# PJ19.net
KiCad netlist of a schematic drawn in EAGLE
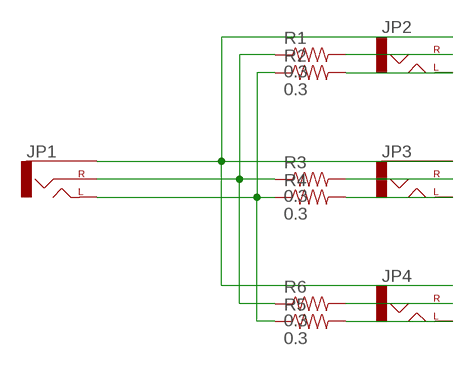
[diagram p0: schematic, sheet 1]

(export (version "E")
  (design (tool "Eeschema 10.0.6"))
  (components
    (comp (ref "JP1")
      (value "AUDIO-JACKPTH")
      (footprint "eagle-import:AUDIO-JACK")
      (libsource (lib "eagle-import") (part "AUDIO-JACKPTH"))
    )
    (comp (ref "JP2")
      (value "AUDIO-JACKPTH")
      (footprint "eagle-import:AUDIO-JACK")
      (libsource (lib "eagle-import") (part "AUDIO-JACKPTH"))
    )
    (comp (ref "JP3")
      (value "AUDIO-JACKPTH")
      (footprint "eagle-import:AUDIO-JACK")
      (libsource (lib "eagle-import") (part "AUDIO-JACKPTH"))
    )
    (comp (ref "JP4")
      (value "AUDIO-JACKPTH")
      (footprint "eagle-import:AUDIO-JACK")
      (libsource (lib "eagle-import") (part "AUDIO-JACKPTH"))
    )
    (comp (ref "R1")
      (value "0.3")
      (footprint "eagle-import:0805")
      (libsource (lib "eagle-import") (part "0.3OHM-1/8W-1%(0805)"))
    )
    (comp (ref "R2")
      (value "0.3")
      (footprint "eagle-import:0805")
      (libsource (lib "eagle-import") (part "0.3OHM-1/8W-1%(0805)"))
    )
    (comp (ref "R3")
      (value "0.3")
      (footprint "eagle-import:0805")
      (libsource (lib "eagle-import") (part "0.3OHM-1/8W-1%(0805)"))
    )
    (comp (ref "R4")
      (value "0.3")
      (footprint "eagle-import:0805")
      (libsource (lib "eagle-import") (part "0.3OHM-1/8W-1%(0805)"))
    )
    (comp (ref "R5")
      (value "0.3")
      (footprint "eagle-import:0805")
      (libsource (lib "eagle-import") (part "0.3OHM-1/8W-1%(0805)"))
    )
    (comp (ref "R6")
      (value "0.3")
      (footprint "eagle-import:0805")
      (libsource (lib "eagle-import") (part "0.3OHM-1/8W-1%(0805)"))
    )
  )
  (nets
    (net (code "1") (name "Net-(JP1-LEFT)") (class "Default")
      (node (ref "JP1") (pin "TIP") (pinfunction "LEFT_TIP") (pintype "bidirectional"))
      (node (ref "R2") (pin "1") (pinfunction "1_1") (pintype "passive"))
      (node (ref "R4") (pin "1") (pinfunction "1_1") (pintype "passive"))
      (node (ref "R5") (pin "1") (pinfunction "1_1") (pintype "passive"))
    )
    (net (code "2") (name "Net-(JP1-PadSLEEVE)") (class "Default")
      (node (ref "JP1") (pin "SLEEVE") (pinfunction "SLEEVE_SLEEVE") (pintype "bidirectional"))
      (node (ref "JP2") (pin "SLEEVE") (pinfunction "SLEEVE_SLEEVE") (pintype "bidirectional"))
      (node (ref "JP3") (pin "SLEEVE") (pinfunction "SLEEVE_SLEEVE") (pintype "bidirectional"))
      (node (ref "JP4") (pin "SLEEVE") (pinfunction "SLEEVE_SLEEVE") (pintype "bidirectional"))
    )
    (net (code "3") (name "Net-(JP1-RIGHT)") (class "Default")
      (node (ref "JP1") (pin "RING") (pinfunction "RIGHT_RING") (pintype "bidirectional"))
      (node (ref "R1") (pin "1") (pinfunction "1_1") (pintype "passive"))
      (node (ref "R3") (pin "1") (pinfunction "1_1") (pintype "passive"))
      (node (ref "R6") (pin "1") (pinfunction "1_1") (pintype "passive"))
    )
    (net (code "4") (name "Net-(JP2-LEFT)") (class "Default")
      (node (ref "JP2") (pin "TIP") (pinfunction "LEFT_TIP") (pintype "bidirectional"))
      (node (ref "R2") (pin "2") (pinfunction "2_2") (pintype "passive"))
    )
    (net (code "5") (name "Net-(JP2-RIGHT)") (class "Default")
      (node (ref "JP2") (pin "RING") (pinfunction "RIGHT_RING") (pintype "bidirectional"))
      (node (ref "R1") (pin "2") (pinfunction "2_2") (pintype "passive"))
    )
    (net (code "6") (name "Net-(JP3-LEFT)") (class "Default")
      (node (ref "JP3") (pin "TIP") (pinfunction "LEFT_TIP") (pintype "bidirectional"))
      (node (ref "R4") (pin "2") (pinfunction "2_2") (pintype "passive"))
    )
    (net (code "7") (name "Net-(JP3-RIGHT)") (class "Default")
      (node (ref "JP3") (pin "RING") (pinfunction "RIGHT_RING") (pintype "bidirectional"))
      (node (ref "R3") (pin "2") (pinfunction "2_2") (pintype "passive"))
    )
    (net (code "8") (name "Net-(JP4-LEFT)") (class "Default")
      (node (ref "JP4") (pin "TIP") (pinfunction "LEFT_TIP") (pintype "bidirectional"))
      (node (ref "R5") (pin "2") (pinfunction "2_2") (pintype "passive"))
    )
    (net (code "9") (name "Net-(JP4-RIGHT)") (class "Default")
      (node (ref "JP4") (pin "RING") (pinfunction "RIGHT_RING") (pintype "bidirectional"))
      (node (ref "R6") (pin "2") (pinfunction "2_2") (pintype "passive"))
    )
  )
)
